# fridge.net
KiCad netlist of a schematic drawn in EAGLE
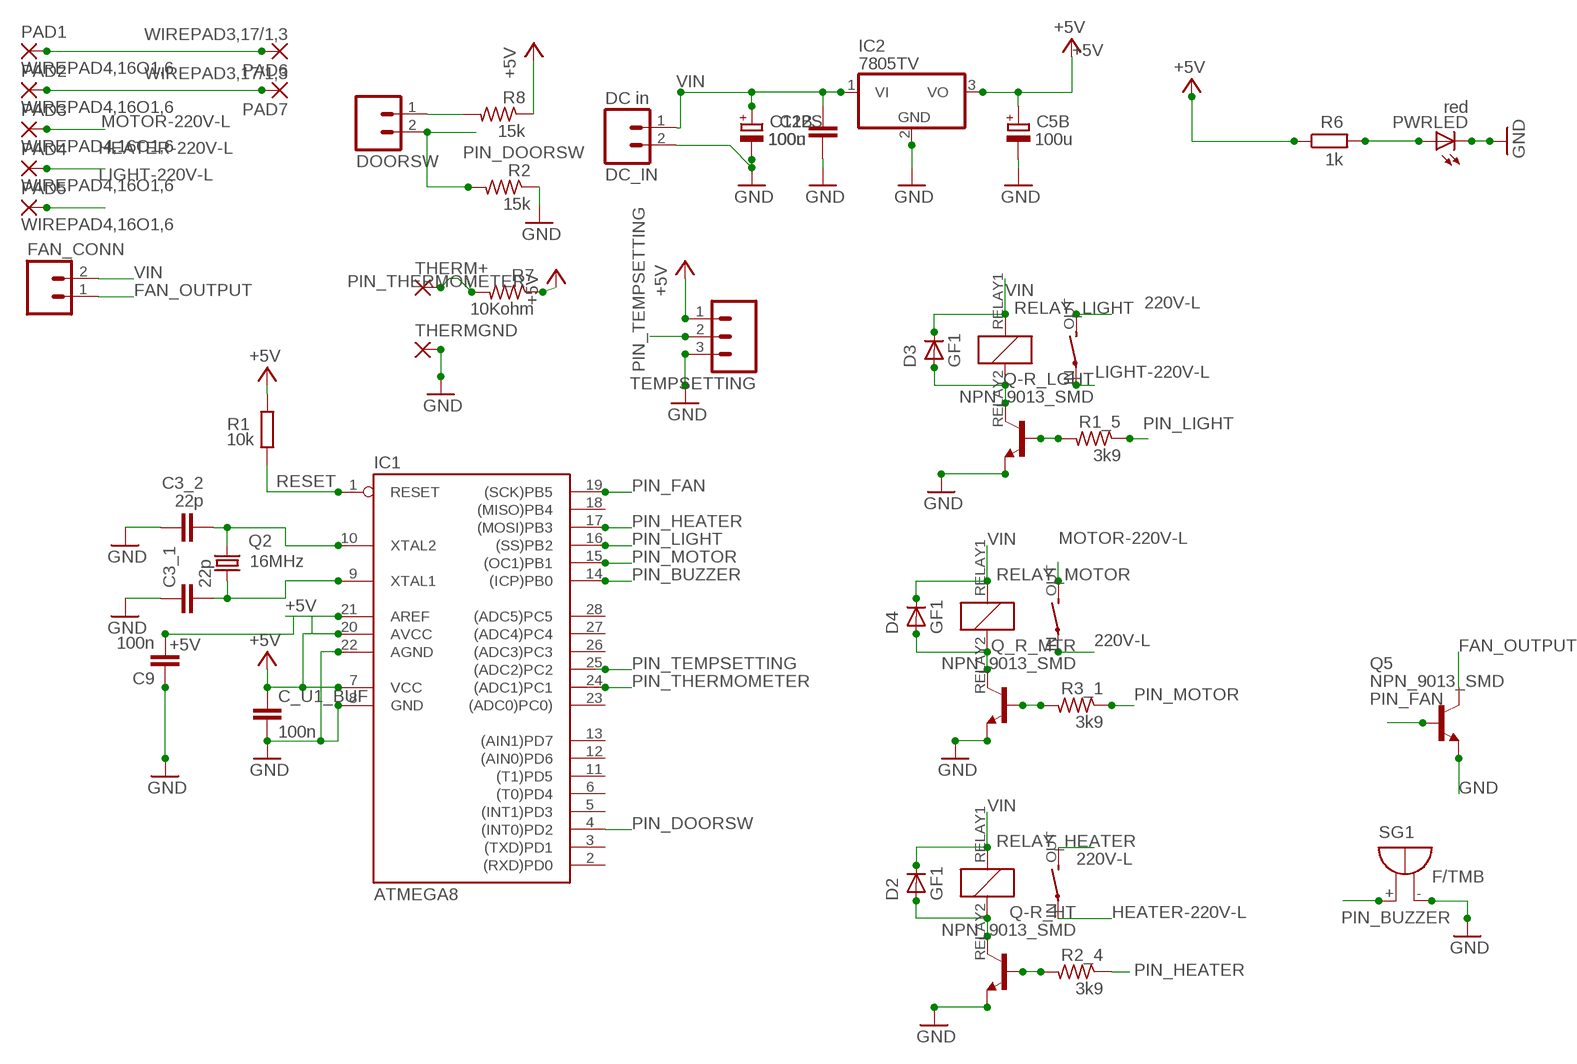
[diagram p0: schematic, sheet 1]

(export (version "E")
  (design (tool "Eeschema 10.0.6"))
  (components
    (comp (ref "C3_1")
      (value "22p")
      (footprint "eagle-import:C025-025X050")
      (libsource (lib "eagle-import") (part "C-EU025-025X050"))
    )
    (comp (ref "C3_2")
      (value "22p")
      (footprint "eagle-import:C025-025X050")
      (libsource (lib "eagle-import") (part "C-EU025-025X050"))
    )
    (comp (ref "C5B")
      (value "100u")
      (footprint "eagle-import:E2,5-7")
      (libsource (lib "eagle-import") (part "CPOL-EUE2.5-7"))
    )
    (comp (ref "C9")
      (value "100n")
      (footprint "eagle-import:C050-030X075")
      (libsource (lib "eagle-import") (part "C-EU050-030X075"))
    )
    (comp (ref "C12B")
      (value "100u")
      (footprint "eagle-import:E2,5-7")
      (libsource (lib "eagle-import") (part "CPOL-EUE2.5-7"))
    )
    (comp (ref "C12S")
      (value "100n")
      (footprint "eagle-import:C050-035X075")
      (libsource (lib "eagle-import") (part "C-EU050-035X075"))
    )
    (comp (ref "C_U1_BUF")
      (value "100n")
      (footprint "eagle-import:C050-035X075")
      (libsource (lib "eagle-import") (part "C-EU050-035X075"))
    )
    (comp (ref "D2")
      (value "GF1")
      (footprint "eagle-import:SMA-DO214AC")
      (libsource (lib "eagle-import") (part "GF1"))
    )
    (comp (ref "D3")
      (value "GF1")
      (footprint "eagle-import:SMA-DO214AC")
      (libsource (lib "eagle-import") (part "GF1"))
    )
    (comp (ref "D4")
      (value "GF1")
      (footprint "eagle-import:SMA-DO214AC")
      (libsource (lib "eagle-import") (part "GF1"))
    )
    (comp (ref "DC_IN")
      (value "DC in")
      (footprint "eagle-import:02P")
      (libsource (lib "eagle-import") (part "M02"))
    )
    (comp (ref "DOORSW")
      (value "M02")
      (footprint "eagle-import:02P")
      (libsource (lib "eagle-import") (part "M02"))
    )
    (comp (ref "FAN_CONN")
      (value "M02")
      (footprint "eagle-import:02P")
      (libsource (lib "eagle-import") (part "M02"))
    )
    (comp (ref "IC1")
      (value "ATMEGA8")
      (footprint "eagle-import:DIL28-3")
      (libsource (lib "eagle-import") (part "AT90S4433P"))
    )
    (comp (ref "IC2")
      (value "7805TV")
      (footprint "eagle-import:TO220V")
      (libsource (lib "eagle-import") (part "78TV05"))
    )
    (comp (ref "PAD1")
      (value "WIREPAD4,16O1,6")
      (footprint "eagle-import:4,16O1,6")
      (libsource (lib "eagle-import") (part "WIREPAD4,16O1,6"))
    )
    (comp (ref "PAD2")
      (value "WIREPAD4,16O1,6")
      (footprint "eagle-import:4,16O1,6")
      (libsource (lib "eagle-import") (part "WIREPAD4,16O1,6"))
    )
    (comp (ref "PAD3")
      (value "WIREPAD4,16O1,6")
      (footprint "eagle-import:4,16O1,6")
      (libsource (lib "eagle-import") (part "WIREPAD4,16O1,6"))
    )
    (comp (ref "PAD4")
      (value "WIREPAD4,16O1,6")
      (footprint "eagle-import:4,16O1,6")
      (libsource (lib "eagle-import") (part "WIREPAD4,16O1,6"))
    )
    (comp (ref "PAD5")
      (value "WIREPAD4,16O1,6")
      (footprint "eagle-import:4,16O1,6")
      (libsource (lib "eagle-import") (part "WIREPAD4,16O1,6"))
    )
    (comp (ref "PAD6")
      (value "WIREPAD3,17/1,3")
      (footprint "eagle-import:3,17_1,3")
      (libsource (lib "eagle-import") (part "WIREPAD3,17/1,3"))
    )
    (comp (ref "PAD7")
      (value "WIREPAD3,17/1,3")
      (footprint "eagle-import:3,17_1,3")
      (libsource (lib "eagle-import") (part "WIREPAD3,17/1,3"))
    )
    (comp (ref "PWRLED")
      (value "red")
      (footprint "eagle-import:LED5MM")
      (libsource (lib "eagle-import") (part "LED5MM"))
    )
    (comp (ref "Q-R_HT")
      (value "NPN_9013_SMD")
      (footprint "eagle-import:TO92")
      (libsource (lib "eagle-import") (part "transistor-neu-to92_BC337"))
    )
    (comp (ref "Q-R_LGHT")
      (value "NPN_9013_SMD")
      (footprint "eagle-import:TO92")
      (libsource (lib "eagle-import") (part "transistor-neu-to92_BC337"))
    )
    (comp (ref "Q2")
      (value "16MHz")
      (footprint "eagle-import:HC49_S")
      (libsource (lib "eagle-import") (part "CRYTALHC49S"))
    )
    (comp (ref "Q5")
      (value "NPN_9013_SMD")
      (footprint "eagle-import:TO92")
      (libsource (lib "eagle-import") (part "BC337"))
    )
    (comp (ref "Q_R_MTR")
      (value "NPN_9013_SMD")
      (footprint "eagle-import:TO92")
      (libsource (lib "eagle-import") (part "transistor-neu-to92_BC337"))
    )
    (comp (ref "R1")
      (value "10k")
      (footprint "eagle-import:0204_7")
      (libsource (lib "eagle-import") (part "R-EU_0204/7"))
    )
    (comp (ref "R1_5")
      (value "3k9")
      (footprint "eagle-import:0204_7")
      (libsource (lib "eagle-import") (part "R-US_0204/7"))
    )
    (comp (ref "R2")
      (value "15k")
      (footprint "eagle-import:0204V")
      (libsource (lib "eagle-import") (part "R-US_0204/2V"))
    )
    (comp (ref "R2_4")
      (value "3k9")
      (footprint "eagle-import:0204_7")
      (libsource (lib "eagle-import") (part "R-US_0204/7"))
    )
    (comp (ref "R3_1")
      (value "3k9")
      (footprint "eagle-import:0204_7")
      (libsource (lib "eagle-import") (part "R-US_0204/7"))
    )
    (comp (ref "R6")
      (value "1k")
      (footprint "eagle-import:0204_7")
      (libsource (lib "eagle-import") (part "R-EU_0204/7"))
    )
    (comp (ref "R7")
      (value "10Kohm")
      (footprint "eagle-import:0204V")
      (libsource (lib "eagle-import") (part "R-US_0204/2V"))
    )
    (comp (ref "R8")
      (value "15k")
      (footprint "eagle-import:0204V")
      (libsource (lib "eagle-import") (part "R-US_0204/2V"))
    )
    (comp (ref "RELAY_HEATER")
      (value "OJE-SS-112HMFSPSTOJE-SS-112HMF")
      (footprint "eagle-import:OJ_OJE_SERIES")
      (libsource (lib "eagle-import") (part "OJE-SS-112HMFOJE-SS-112HMFSPST"))
    )
    (comp (ref "RELAY_LIGHT")
      (value "OJE-SS-112HMFSPSTOJE-SS-112HMF")
      (footprint "eagle-import:OJ_OJE_SERIES")
      (libsource (lib "eagle-import") (part "OJE-SS-112HMFOJE-SS-112HMFSPST"))
    )
    (comp (ref "RELAY_MOTOR")
      (value "OJE-SS-112HMFSPSTOJE-SS-112HMF")
      (footprint "eagle-import:OJ_OJE_SERIES")
      (libsource (lib "eagle-import") (part "OJE-SS-112HMFOJE-SS-112HMFSPST"))
    )
    (comp (ref "SG1")
      (value "F/TMB")
      (footprint "eagle-import:F_TMB")
      (libsource (lib "eagle-import") (part "F/TMB"))
    )
    (comp (ref "TEMPSETTING")
      (value "M03")
      (footprint "eagle-import:03P")
      (libsource (lib "eagle-import") (part "M03"))
    )
    (comp (ref "THERM+")
      (value "1,6/0,9")
      (footprint "eagle-import:1,6_0,9")
      (libsource (lib "eagle-import") (part "1,6/0,9"))
    )
    (comp (ref "THERMGND")
      (value "1,6/0,9")
      (footprint "eagle-import:1,6_0,9")
      (libsource (lib "eagle-import") (part "1,6/0,9"))
    )
  )
  (nets
    (net (code "1") (name "+5V") (class "Default")
      (node (ref "C5B") (pin "+") (pinfunction "+_+") (pintype "passive"))
      (node (ref "C9") (pin "2") (pinfunction "2_2") (pintype "passive"))
      (node (ref "C_U1_BUF") (pin "1") (pinfunction "1_1") (pintype "passive"))
      (node (ref "IC1") (pin "20") (pinfunction "AVCC_20") (pintype "power_in"))
      (node (ref "IC1") (pin "21") (pinfunction "AREF_21") (pintype "passive"))
      (node (ref "IC1") (pin "7") (pinfunction "VCC_7") (pintype "power_in"))
      (node (ref "IC2") (pin "3") (pinfunction "VO_3") (pintype "passive"))
      (node (ref "R1") (pin "2") (pinfunction "2_2") (pintype "passive"))
      (node (ref "R6") (pin "1") (pinfunction "1_1") (pintype "passive"))
      (node (ref "R7") (pin "1") (pinfunction "1_1") (pintype "passive"))
      (node (ref "R8") (pin "1") (pinfunction "1_1") (pintype "passive"))
      (node (ref "TEMPSETTING") (pin "1") (pinfunction "1_1") (pintype "passive"))
    )
    (net (code "2") (name "/220V-L") (class "Default")
      (node (ref "PAD1") (pin "1") (pinfunction "P_1") (pintype "passive"))
      (node (ref "PAD6") (pin "1") (pinfunction "P_1") (pintype "passive"))
      (node (ref "RELAY_HEATER") (pin "OUT") (pinfunction "OUT_OUT") (pintype "passive"))
      (node (ref "RELAY_LIGHT") (pin "OUT") (pinfunction "OUT_OUT") (pintype "passive"))
      (node (ref "RELAY_MOTOR") (pin "IN") (pinfunction "IN_IN") (pintype "passive"))
    )
    (net (code "3") (name "/FAN_OUTPUT") (class "Default")
      (node (ref "FAN_CONN") (pin "1") (pinfunction "1_1") (pintype "passive"))
      (node (ref "Q5") (pin "3") (pinfunction "C_3") (pintype "passive"))
    )
    (net (code "4") (name "/HEATER-220V-L") (class "Default")
      (node (ref "PAD4") (pin "1") (pinfunction "P_1") (pintype "passive"))
      (node (ref "RELAY_HEATER") (pin "IN") (pinfunction "IN_IN") (pintype "passive"))
    )
    (net (code "5") (name "/LIGHT-220V-L") (class "Default")
      (node (ref "PAD5") (pin "1") (pinfunction "P_1") (pintype "passive"))
      (node (ref "RELAY_LIGHT") (pin "IN") (pinfunction "IN_IN") (pintype "passive"))
    )
    (net (code "6") (name "/MOTOR-220V-L") (class "Default")
      (node (ref "PAD3") (pin "1") (pinfunction "P_1") (pintype "passive"))
      (node (ref "RELAY_MOTOR") (pin "OUT") (pinfunction "OUT_OUT") (pintype "passive"))
    )
    (net (code "7") (name "/PIN_BUZZER") (class "Default")
      (node (ref "IC1") (pin "14") (pinfunction "(ICP)PB0_14") (pintype "bidirectional"))
      (node (ref "SG1") (pin "+") (pinfunction "+_+") (pintype "passive"))
    )
    (net (code "8") (name "/PIN_DOORSW") (class "Default")
      (node (ref "DOORSW") (pin "2") (pinfunction "2_2") (pintype "passive"))
      (node (ref "IC1") (pin "4") (pinfunction "(INT0)PD2_4") (pintype "bidirectional"))
      (node (ref "R2") (pin "2") (pinfunction "2_2") (pintype "passive"))
    )
    (net (code "9") (name "/PIN_FAN") (class "Default")
      (node (ref "IC1") (pin "19") (pinfunction "(SCK)PB5_19") (pintype "bidirectional"))
      (node (ref "Q5") (pin "2") (pinfunction "B_2") (pintype "passive"))
    )
    (net (code "10") (name "/PIN_HEATER") (class "Default")
      (node (ref "IC1") (pin "17") (pinfunction "(MOSI)PB3_17") (pintype "bidirectional"))
      (node (ref "R2_4") (pin "1") (pinfunction "1_1") (pintype "passive"))
    )
    (net (code "11") (name "/PIN_LIGHT") (class "Default")
      (node (ref "IC1") (pin "16") (pinfunction "(SS)PB2_16") (pintype "bidirectional"))
      (node (ref "R1_5") (pin "1") (pinfunction "1_1") (pintype "passive"))
    )
    (net (code "12") (name "/PIN_MOTOR") (class "Default")
      (node (ref "IC1") (pin "15") (pinfunction "(OC1)PB1_15") (pintype "bidirectional"))
      (node (ref "R3_1") (pin "1") (pinfunction "1_1") (pintype "passive"))
    )
    (net (code "13") (name "/PIN_TEMPSETTING") (class "Default")
      (node (ref "IC1") (pin "25") (pinfunction "(ADC2)PC2_25") (pintype "bidirectional"))
      (node (ref "TEMPSETTING") (pin "2") (pinfunction "2_2") (pintype "passive"))
    )
    (net (code "14") (name "/PIN_THERMOMETER") (class "Default")
      (node (ref "IC1") (pin "24") (pinfunction "(ADC1)PC1_24") (pintype "bidirectional"))
      (node (ref "R7") (pin "2") (pinfunction "2_2") (pintype "passive"))
      (node (ref "THERM+") (pin "1") (pinfunction "P_1") (pintype "passive"))
    )
    (net (code "15") (name "/RESET") (class "Default")
      (node (ref "IC1") (pin "1") (pinfunction "RESET_1") (pintype "input"))
      (node (ref "R1") (pin "1") (pinfunction "1_1") (pintype "passive"))
    )
    (net (code "16") (name "/VIN") (class "Default")
      (node (ref "C12B") (pin "+") (pinfunction "+_+") (pintype "passive"))
      (node (ref "C12S") (pin "2") (pinfunction "2_2") (pintype "passive"))
      (node (ref "D2") (pin "K") (pinfunction "C_K") (pintype "passive"))
      (node (ref "D3") (pin "K") (pinfunction "C_K") (pintype "passive"))
      (node (ref "D4") (pin "K") (pinfunction "C_K") (pintype "passive"))
      (node (ref "DC_IN") (pin "1") (pinfunction "1_1") (pintype "passive"))
      (node (ref "FAN_CONN") (pin "2") (pinfunction "2_2") (pintype "passive"))
      (node (ref "IC2") (pin "1") (pinfunction "VI_1") (pintype "input"))
      (node (ref "RELAY_HEATER") (pin "RELAY1") (pinfunction "RELAY_1_RELAY1") (pintype "passive"))
      (node (ref "RELAY_LIGHT") (pin "RELAY1") (pinfunction "RELAY_1_RELAY1") (pintype "passive"))
      (node (ref "RELAY_MOTOR") (pin "RELAY1") (pinfunction "RELAY_1_RELAY1") (pintype "passive"))
    )
    (net (code "17") (name "GND") (class "Default")
      (node (ref "C12B") (pin "-") (pinfunction "-_-") (pintype "passive"))
      (node (ref "C12S") (pin "1") (pinfunction "1_1") (pintype "passive"))
      (node (ref "C3_1") (pin "1") (pinfunction "1_1") (pintype "passive"))
      (node (ref "C3_2") (pin "1") (pinfunction "1_1") (pintype "passive"))
      (node (ref "C5B") (pin "-") (pinfunction "-_-") (pintype "passive"))
      (node (ref "C9") (pin "1") (pinfunction "1_1") (pintype "passive"))
      (node (ref "C_U1_BUF") (pin "2") (pinfunction "2_2") (pintype "passive"))
      (node (ref "DC_IN") (pin "2") (pinfunction "2_2") (pintype "passive"))
      (node (ref "IC1") (pin "22") (pinfunction "AGND_22") (pintype "power_in"))
      (node (ref "IC1") (pin "8") (pinfunction "GND_8") (pintype "power_in"))
      (node (ref "IC2") (pin "2") (pinfunction "GND_2") (pintype "passive"))
      (node (ref "PWRLED") (pin "K") (pinfunction "C_K") (pintype "passive"))
      (node (ref "Q-R_HT") (pin "1") (pinfunction "E_1") (pintype "passive"))
      (node (ref "Q-R_LGHT") (pin "1") (pinfunction "E_1") (pintype "passive"))
      (node (ref "Q5") (pin "1") (pinfunction "E_1") (pintype "passive"))
      (node (ref "Q_R_MTR") (pin "1") (pinfunction "E_1") (pintype "passive"))
      (node (ref "R2") (pin "1") (pinfunction "1_1") (pintype "passive"))
      (node (ref "SG1") (pin "-") (pinfunction "-_-") (pintype "passive"))
      (node (ref "TEMPSETTING") (pin "3") (pinfunction "3_3") (pintype "passive"))
      (node (ref "THERMGND") (pin "1") (pinfunction "P_1") (pintype "passive"))
    )
    (net (code "18") (name "Net-(DOORSW-Pad1)") (class "Default")
      (node (ref "DOORSW") (pin "1") (pinfunction "1_1") (pintype "passive"))
      (node (ref "R8") (pin "2") (pinfunction "2_2") (pintype "passive"))
    )
    (net (code "19") (name "Net-(IC1-XTAL1)") (class "Default")
      (node (ref "C3_1") (pin "2") (pinfunction "2_2") (pintype "passive"))
      (node (ref "IC1") (pin "9") (pinfunction "XTAL1_9") (pintype "bidirectional"))
      (node (ref "Q2") (pin "1") (pinfunction "1_1") (pintype "passive"))
    )
    (net (code "20") (name "Net-(IC1-XTAL2)") (class "Default")
      (node (ref "C3_2") (pin "2") (pinfunction "2_2") (pintype "passive"))
      (node (ref "IC1") (pin "10") (pinfunction "XTAL2_10") (pintype "bidirectional"))
      (node (ref "Q2") (pin "2") (pinfunction "2_2") (pintype "passive"))
    )
    (net (code "21") (name "Net-(PAD2-P)") (class "Default")
      (node (ref "PAD2") (pin "1") (pinfunction "P_1") (pintype "passive"))
      (node (ref "PAD7") (pin "1") (pinfunction "P_1") (pintype "passive"))
    )
    (net (code "22") (name "Net-(PWRLED-PadA)") (class "Default")
      (node (ref "PWRLED") (pin "A") (pinfunction "A_A") (pintype "passive"))
      (node (ref "R6") (pin "2") (pinfunction "2_2") (pintype "passive"))
    )
    (net (code "23") (name "Net-(Q-R_HT-B)") (class "Default")
      (node (ref "Q-R_HT") (pin "2") (pinfunction "B_2") (pintype "passive"))
      (node (ref "R2_4") (pin "2") (pinfunction "2_2") (pintype "passive"))
    )
    (net (code "24") (name "Net-(Q-R_HT-C)") (class "Default")
      (node (ref "D2") (pin "A") (pinfunction "A_A") (pintype "passive"))
      (node (ref "Q-R_HT") (pin "3") (pinfunction "C_3") (pintype "passive"))
      (node (ref "RELAY_HEATER") (pin "RELAY2") (pinfunction "RELAY_2_RELAY2") (pintype "passive"))
    )
    (net (code "25") (name "Net-(Q-R_LGHT-B)") (class "Default")
      (node (ref "Q-R_LGHT") (pin "2") (pinfunction "B_2") (pintype "passive"))
      (node (ref "R1_5") (pin "2") (pinfunction "2_2") (pintype "passive"))
    )
    (net (code "26") (name "Net-(Q-R_LGHT-C)") (class "Default")
      (node (ref "D3") (pin "A") (pinfunction "A_A") (pintype "passive"))
      (node (ref "Q-R_LGHT") (pin "3") (pinfunction "C_3") (pintype "passive"))
      (node (ref "RELAY_LIGHT") (pin "RELAY2") (pinfunction "RELAY_2_RELAY2") (pintype "passive"))
    )
    (net (code "27") (name "Net-(Q_R_MTR-B)") (class "Default")
      (node (ref "Q_R_MTR") (pin "2") (pinfunction "B_2") (pintype "passive"))
      (node (ref "R3_1") (pin "2") (pinfunction "2_2") (pintype "passive"))
    )
    (net (code "28") (name "Net-(Q_R_MTR-C)") (class "Default")
      (node (ref "D4") (pin "A") (pinfunction "A_A") (pintype "passive"))
      (node (ref "Q_R_MTR") (pin "3") (pinfunction "C_3") (pintype "passive"))
      (node (ref "RELAY_MOTOR") (pin "RELAY2") (pinfunction "RELAY_2_RELAY2") (pintype "passive"))
    )
    (net (code "29") (name "unconnected-(IC1-(ADC0)PC0)-Pad23)") (class "Default")
      (node (ref "IC1") (pin "23") (pinfunction "(ADC0)PC0)_23") (pintype "bidirectional"))
    )
    (net (code "30") (name "unconnected-(IC1-(ADC3)PC3-Pad26)") (class "Default")
      (node (ref "IC1") (pin "26") (pinfunction "(ADC3)PC3_26") (pintype "bidirectional"))
    )
    (net (code "31") (name "unconnected-(IC1-(ADC4)PC4-Pad27)") (class "Default")
      (node (ref "IC1") (pin "27") (pinfunction "(ADC4)PC4_27") (pintype "bidirectional"))
    )
    (net (code "32") (name "unconnected-(IC1-(ADC5)PC5-Pad28)") (class "Default")
      (node (ref "IC1") (pin "28") (pinfunction "(ADC5)PC5_28") (pintype "bidirectional"))
    )
    (net (code "33") (name "unconnected-(IC1-(AIN0)PD6-Pad12)") (class "Default")
      (node (ref "IC1") (pin "12") (pinfunction "(AIN0)PD6_12") (pintype "bidirectional"))
    )
    (net (code "34") (name "unconnected-(IC1-(AIN1)PD7-Pad13)") (class "Default")
      (node (ref "IC1") (pin "13") (pinfunction "(AIN1)PD7_13") (pintype "bidirectional"))
    )
    (net (code "35") (name "unconnected-(IC1-(INT1)PD3-Pad5)") (class "Default")
      (node (ref "IC1") (pin "5") (pinfunction "(INT1)PD3_5") (pintype "bidirectional"))
    )
    (net (code "36") (name "unconnected-(IC1-(MISO)PB4-Pad18)") (class "Default")
      (node (ref "IC1") (pin "18") (pinfunction "(MISO)PB4_18") (pintype "bidirectional"))
    )
    (net (code "37") (name "unconnected-(IC1-(RXD)PD0-Pad2)") (class "Default")
      (node (ref "IC1") (pin "2") (pinfunction "(RXD)PD0_2") (pintype "bidirectional"))
    )
    (net (code "38") (name "unconnected-(IC1-(T0)PD4-Pad6)") (class "Default")
      (node (ref "IC1") (pin "6") (pinfunction "(T0)PD4_6") (pintype "bidirectional"))
    )
    (net (code "39") (name "unconnected-(IC1-(T1)PD5-Pad11)") (class "Default")
      (node (ref "IC1") (pin "11") (pinfunction "(T1)PD5_11") (pintype "bidirectional"))
    )
    (net (code "40") (name "unconnected-(IC1-(TXD)PD1-Pad3)") (class "Default")
      (node (ref "IC1") (pin "3") (pinfunction "(TXD)PD1_3") (pintype "bidirectional"))
    )
  )
)
